# LVDS.net
KiCad netlist of a schematic drawn in Altium Designer
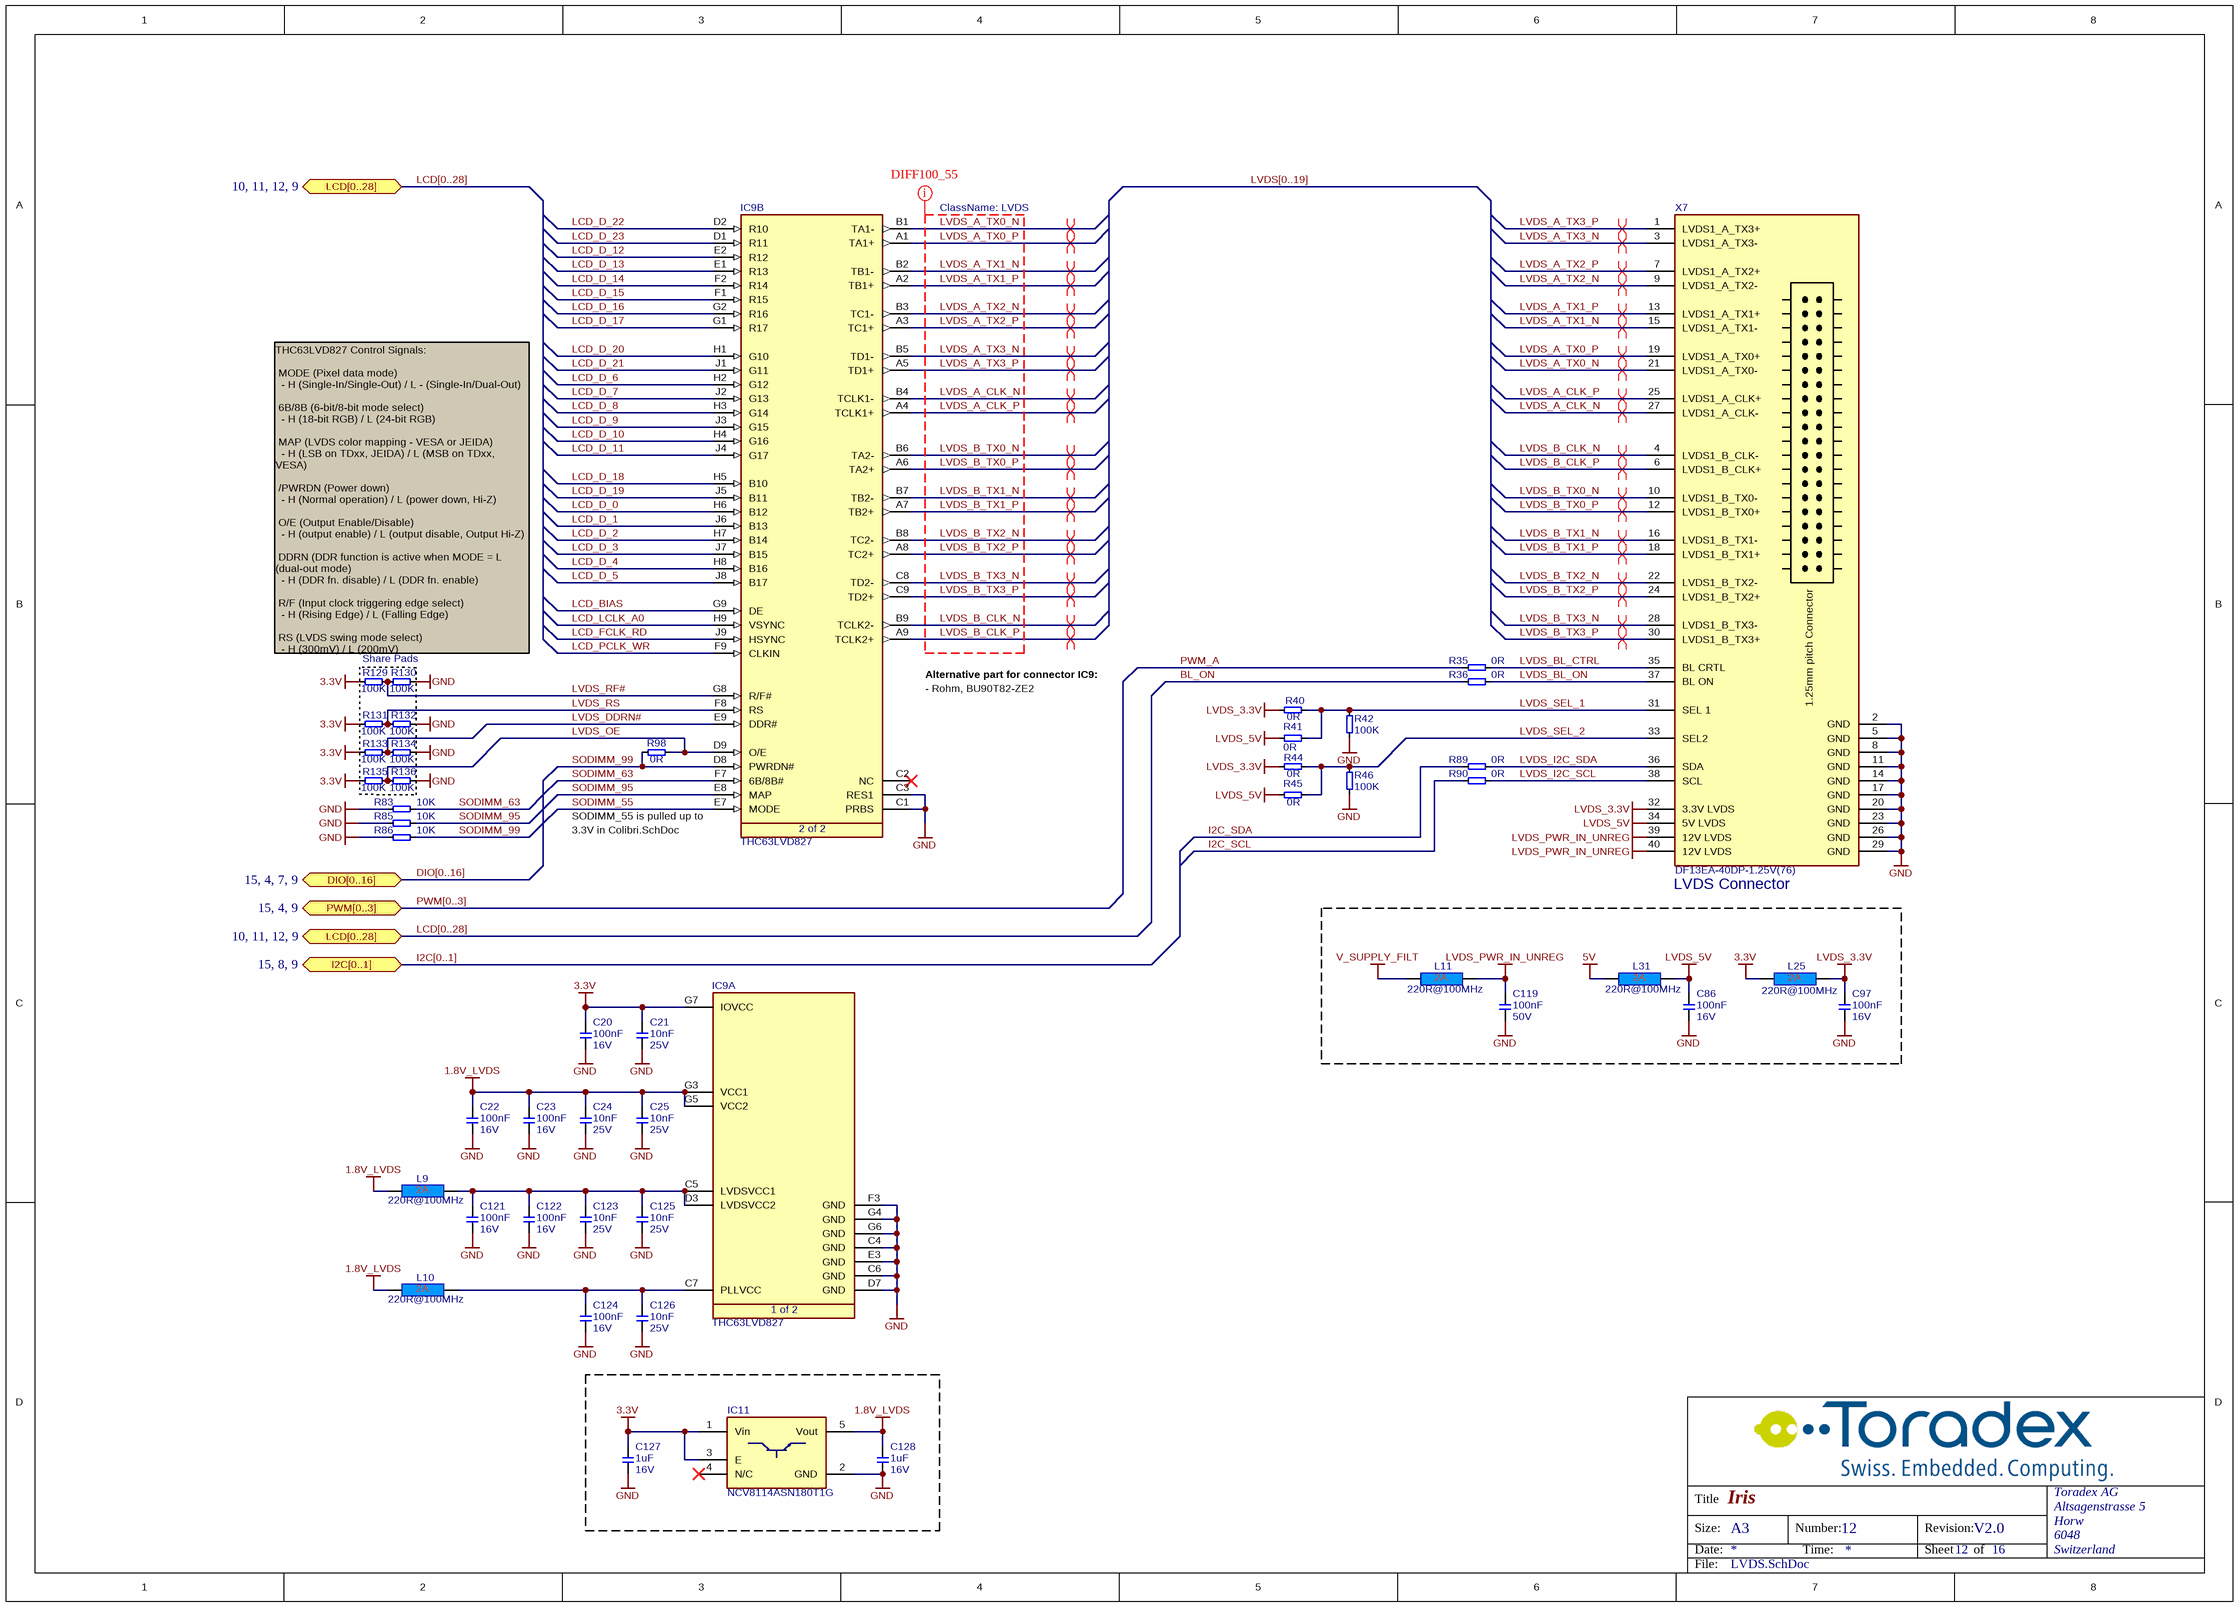
[diagram p0: LVDS.SchDoc]

(export (version "E")
  (design (tool "Eeschema 10.0.6"))
  (components
    (comp (ref "C20")
      (value "100nF")
      (footprint "CAPC1005X60N")
      (description "Capacitor Ceramic X7R 100nF 16V 10% 0402")
      (fields (field (name "TOLERANCE") "10%") (field (name "RATING") "16V"))
      (libsource (lib "Iris") (part "C-X7R-100nF-16V-10%-0402"))
    )
    (comp (ref "C21")
      (value "10nF")
      (footprint "CAPC1005X60N")
      (description "Capacitor Ceramic X7R 10nF 25V 10% 0402")
      (fields (field (name "TOLERANCE") "10%") (field (name "RATING") "25V"))
      (libsource (lib "Iris") (part "C-X7R-10nF-25V-10%-0402"))
    )
    (comp (ref "C22")
      (value "100nF")
      (footprint "CAPC1005X60N")
      (description "Capacitor Ceramic X7R 100nF 16V 10% 0402")
      (fields (field (name "TOLERANCE") "10%") (field (name "RATING") "16V"))
      (libsource (lib "Iris") (part "C-X7R-100nF-16V-10%-0402"))
    )
    (comp (ref "C23")
      (value "100nF")
      (footprint "CAPC1005X60N")
      (description "Capacitor Ceramic X7R 100nF 16V 10% 0402")
      (fields (field (name "TOLERANCE") "10%") (field (name "RATING") "16V"))
      (libsource (lib "Iris") (part "C-X7R-100nF-16V-10%-0402"))
    )
    (comp (ref "C24")
      (value "10nF")
      (footprint "CAPC1005X60N")
      (description "Capacitor Ceramic X7R 10nF 25V 10% 0402")
      (fields (field (name "TOLERANCE") "10%") (field (name "RATING") "25V"))
      (libsource (lib "Iris") (part "C-X7R-10nF-25V-10%-0402"))
    )
    (comp (ref "C25")
      (value "10nF")
      (footprint "CAPC1005X60N")
      (description "Capacitor Ceramic X7R 10nF 25V 10% 0402")
      (fields (field (name "TOLERANCE") "10%") (field (name "RATING") "25V"))
      (libsource (lib "Iris") (part "C-X7R-10nF-25V-10%-0402"))
    )
    (comp (ref "C86")
      (value "100nF")
      (footprint "CAPC1005X60N")
      (description "Capacitor Ceramic X7R 100nF 16V 10% 0402")
      (fields (field (name "TOLERANCE") "10%") (field (name "RATING") "16V"))
      (libsource (lib "Iris") (part "C-X7R-100nF-16V-10%-0402"))
    )
    (comp (ref "C97")
      (value "100nF")
      (footprint "CAPC1005X60N")
      (description "Capacitor Ceramic X7R 100nF 16V 10% 0402")
      (fields (field (name "TOLERANCE") "10%") (field (name "RATING") "16V"))
      (libsource (lib "Iris") (part "C-X7R-100nF-16V-10%-0402"))
    )
    (comp (ref "C119")
      (value "100nF")
      (footprint "T_CAPC0603X33N")
      (description "Capacitor Ceramic X7R 100nF 50V 10% 0603")
      (fields (field (name "TOLERANCE") "10%") (field (name "RATING") "50V"))
      (libsource (lib "Iris") (part "C-X7R-100nF-50V-10%-0603"))
    )
    (comp (ref "C121")
      (value "100nF")
      (footprint "CAPC1005X60N")
      (description "Capacitor Ceramic X7R 100nF 16V 10% 0402")
      (fields (field (name "TOLERANCE") "10%") (field (name "RATING") "16V"))
      (libsource (lib "Iris") (part "C-X7R-100nF-16V-10%-0402"))
    )
    (comp (ref "C122")
      (value "100nF")
      (footprint "CAPC1005X60N")
      (description "Capacitor Ceramic X7R 100nF 16V 10% 0402")
      (fields (field (name "TOLERANCE") "10%") (field (name "RATING") "16V"))
      (libsource (lib "Iris") (part "C-X7R-100nF-16V-10%-0402"))
    )
    (comp (ref "C123")
      (value "10nF")
      (footprint "CAPC1005X60N")
      (description "Capacitor Ceramic X7R 10nF 25V 10% 0402")
      (fields (field (name "TOLERANCE") "10%") (field (name "RATING") "25V"))
      (libsource (lib "Iris") (part "C-X7R-10nF-25V-10%-0402"))
    )
    (comp (ref "C124")
      (value "100nF")
      (footprint "CAPC1005X60N")
      (description "Capacitor Ceramic X7R 100nF 16V 10% 0402")
      (fields (field (name "TOLERANCE") "10%") (field (name "RATING") "16V"))
      (libsource (lib "Iris") (part "C-X7R-100nF-16V-10%-0402"))
    )
    (comp (ref "C125")
      (value "10nF")
      (footprint "CAPC1005X60N")
      (description "Capacitor Ceramic X7R 10nF 25V 10% 0402")
      (fields (field (name "TOLERANCE") "10%") (field (name "RATING") "25V"))
      (libsource (lib "Iris") (part "C-X7R-10nF-25V-10%-0402"))
    )
    (comp (ref "C126")
      (value "10nF")
      (footprint "CAPC1005X60N")
      (description "Capacitor Ceramic X7R 10nF 25V 10% 0402")
      (fields (field (name "TOLERANCE") "10%") (field (name "RATING") "25V"))
      (libsource (lib "Iris") (part "C-X7R-10nF-25V-10%-0402"))
    )
    (comp (ref "C127")
      (value "1uF")
      (footprint "T_CAPC0603X33N")
      (description "Capacitor Ceramic X5R 1uF 16V 10% 0603")
      (fields (field (name "TOLERANCE") "10%") (field (name "RATING") "16V"))
      (libsource (lib "Iris") (part "C-X5R-1uF-16V-10%-0603"))
    )
    (comp (ref "C128")
      (value "1uF")
      (footprint "T_CAPC0603X33N")
      (description "Capacitor Ceramic X5R 1uF 16V 10% 0603")
      (fields (field (name "TOLERANCE") "10%") (field (name "RATING") "16V"))
      (libsource (lib "Iris") (part "C-X5R-1uF-16V-10%-0603"))
    )
    (comp (ref "IC9")
      (value "THC63LVD827")
      (footprint "BGA72C65P9X9_700X700X120")
      (description "LVDS Transmitter")
      (fields (field (name "MANUFACTURER PART NO.") "THC63LVD827"))
      (libsource (lib "Iris") (part "IC-THine-THC63LVD827"))
    )
    (comp (ref "IC11")
      (value "NCV8114ASN180T1G")
      (footprint "SOT95P279X142-5N")
      (description "LDO regulator, Vout = 1.8V, Imax = 300mA")
      (fields (field (name "MANUFACTURER PART NO.") "NCV8114ASN180T1G"))
      (libsource (lib "Iris") (part "IC-OnSemi-NCV8114ASN180T1G"))
    )
    (comp (ref "L9")
      (value "220R@100MHz")
      (footprint "INDC1608X95N")
      (description "220R@100MHz 2A EMI FILTER")
      (fields (field (name "TOLERANCE") "25%"))
      (libsource (lib "Iris") (part "L-220R@100MHz-2A-25%-0603"))
    )
    (comp (ref "L10")
      (value "220R@100MHz")
      (footprint "INDC1608X95N")
      (description "220R@100MHz 2A EMI FILTER")
      (fields (field (name "TOLERANCE") "25%"))
      (libsource (lib "Iris") (part "L-220R@100MHz-2A-25%-0603"))
    )
    (comp (ref "L11")
      (value "220R@100MHz")
      (footprint "INDC1608X95N")
      (description "220R@100MHz 2A EMI FILTER")
      (fields (field (name "TOLERANCE") "25%"))
      (libsource (lib "Iris") (part "L-220R@100MHz-2A-25%-0603"))
    )
    (comp (ref "L25")
      (value "220R@100MHz")
      (footprint "INDC1608X95N")
      (description "220R@100MHz 2A EMI FILTER")
      (fields (field (name "TOLERANCE") "25%"))
      (libsource (lib "Iris") (part "L-220R@100MHz-2A-25%-0603"))
    )
    (comp (ref "L31")
      (value "220R@100MHz")
      (footprint "INDC1608X95N")
      (description "220R@100MHz 2A EMI FILTER")
      (fields (field (name "TOLERANCE") "25%"))
      (libsource (lib "Iris") (part "L-220R@100MHz-2A-25%-0603"))
    )
    (comp (ref "R35")
      (value "0R")
      (footprint "T_RESC0603X30N")
      (description "Resistor 0 ohm 63mW 5% 0603")
      (fields (field (name "TOLERANCE") "5%"))
      (libsource (lib "Iris") (part "R-0R-63mW-5%-0603"))
    )
    (comp (ref "R36")
      (value "0R")
      (footprint "T_RESC0603X30N")
      (description "Resistor 0 ohm 63mW 5% 0603")
      (fields (field (name "TOLERANCE") "5%"))
      (libsource (lib "Iris") (part "R-0R-63mW-5%-0603"))
    )
    (comp (ref "R40")
      (value "0R")
      (footprint "T_RESC0603X30N")
      (description "Resistor 0 ohm 63mW 5% 0603")
      (fields (field (name "TOLERANCE") "5%"))
      (libsource (lib "Iris") (part "R-0R-63mW-5%-0603"))
    )
    (comp (ref "R41")
      (value "0R")
      (footprint "T_RESC0603X30N")
      (description "Resistor 0 ohm 63mW 5% 0603")
      (fields (field (name "TOLERANCE") "5%"))
      (libsource (lib "Iris") (part "R-0R-63mW-5%-0603"))
    )
    (comp (ref "R42")
      (value "100K")
      (footprint "T_RESC0603X30N")
      (description "Resistor 100 Kohm 63mW 5% 0603")
      (fields (field (name "TOLERANCE") "5%"))
      (libsource (lib "Iris") (part "R-100KR-63mW-5%-0603"))
    )
    (comp (ref "R44")
      (value "0R")
      (footprint "T_RESC0603X30N")
      (description "Resistor 0 ohm 63mW 5% 0603")
      (fields (field (name "TOLERANCE") "5%"))
      (libsource (lib "Iris") (part "R-0R-63mW-5%-0603"))
    )
    (comp (ref "R45")
      (value "0R")
      (footprint "T_RESC0603X30N")
      (description "Resistor 0 ohm 63mW 5% 0603")
      (fields (field (name "TOLERANCE") "5%"))
      (libsource (lib "Iris") (part "R-0R-63mW-5%-0603"))
    )
    (comp (ref "R46")
      (value "100K")
      (footprint "T_RESC0603X30N")
      (description "Resistor 100 Kohm 63mW 5% 0603")
      (fields (field (name "TOLERANCE") "5%"))
      (libsource (lib "Iris") (part "R-100KR-63mW-5%-0603"))
    )
    (comp (ref "R83")
      (value "10K")
      (footprint "T_RESC0603X30N")
      (description "Resistor 10 Kohm 63mW 5% 0603")
      (fields (field (name "TOLERANCE") "5%"))
      (libsource (lib "Iris") (part "R-10KR-63mW-5%-0603"))
    )
    (comp (ref "R85")
      (value "10K")
      (footprint "T_RESC0603X30N")
      (description "Resistor 10 Kohm 63mW 5% 0603")
      (fields (field (name "TOLERANCE") "5%"))
      (libsource (lib "Iris") (part "R-10KR-63mW-5%-0603"))
    )
    (comp (ref "R86")
      (value "10K")
      (footprint "T_RESC0603X30N")
      (description "Resistor 10 Kohm 63mW 5% 0603")
      (fields (field (name "TOLERANCE") "5%"))
      (libsource (lib "Iris") (part "R-10KR-63mW-5%-0603"))
    )
    (comp (ref "R89")
      (value "0R")
      (footprint "T_RESC0603X30N")
      (description "Resistor 0 ohm 63mW 5% 0603")
      (fields (field (name "TOLERANCE") "5%"))
      (libsource (lib "Iris") (part "R-0R-63mW-5%-0603"))
    )
    (comp (ref "R90")
      (value "0R")
      (footprint "T_RESC0603X30N")
      (description "Resistor 0 ohm 63mW 5% 0603")
      (fields (field (name "TOLERANCE") "5%"))
      (libsource (lib "Iris") (part "R-0R-63mW-5%-0603"))
    )
    (comp (ref "R98")
      (value "0R")
      (footprint "T_RESC0603X30N")
      (description "Resistor 0 ohm 63mW 5% 0603")
      (fields (field (name "TOLERANCE") "5%"))
      (libsource (lib "Iris") (part "R-0R-63mW-5%-0603"))
    )
    (comp (ref "R129")
      (value "100K")
      (footprint "T_RESC0603X30N")
      (description "Resistor 100 Kohm 63mW 5% 0603")
      (fields (field (name "TOLERANCE") "5%"))
      (libsource (lib "Iris") (part "R-100KR-63mW-5%-0603"))
    )
    (comp (ref "R130")
      (value "100K")
      (footprint "T_RESC0603X30N")
      (description "Resistor 100 Kohm 63mW 5% 0603")
      (fields (field (name "TOLERANCE") "5%"))
      (libsource (lib "Iris") (part "R-100KR-63mW-5%-0603"))
    )
    (comp (ref "R131")
      (value "100K")
      (footprint "T_RESC0603X30N")
      (description "Resistor 100 Kohm 63mW 5% 0603")
      (fields (field (name "TOLERANCE") "5%"))
      (libsource (lib "Iris") (part "R-100KR-63mW-5%-0603"))
    )
    (comp (ref "R132")
      (value "100K")
      (footprint "T_RESC0603X30N")
      (description "Resistor 100 Kohm 63mW 5% 0603")
      (fields (field (name "TOLERANCE") "5%"))
      (libsource (lib "Iris") (part "R-100KR-63mW-5%-0603"))
    )
    (comp (ref "R133")
      (value "100K")
      (footprint "T_RESC0603X30N")
      (description "Resistor 100 Kohm 63mW 5% 0603")
      (fields (field (name "TOLERANCE") "5%"))
      (libsource (lib "Iris") (part "R-100KR-63mW-5%-0603"))
    )
    (comp (ref "R134")
      (value "100K")
      (footprint "T_RESC0603X30N")
      (description "Resistor 100 Kohm 63mW 5% 0603")
      (fields (field (name "TOLERANCE") "5%"))
      (libsource (lib "Iris") (part "R-100KR-63mW-5%-0603"))
    )
    (comp (ref "R135")
      (value "100K")
      (footprint "T_RESC0603X30N")
      (description "Resistor 100 Kohm 63mW 5% 0603")
      (fields (field (name "TOLERANCE") "5%"))
      (libsource (lib "Iris") (part "R-100KR-63mW-5%-0603"))
    )
    (comp (ref "R136")
      (value "100K")
      (footprint "T_RESC0603X30N")
      (description "Resistor 100 Kohm 63mW 5% 0603")
      (fields (field (name "TOLERANCE") "5%"))
      (libsource (lib "Iris") (part "R-100KR-63mW-5%-0603"))
    )
    (comp (ref "X7")
      (value "DF13EA-40DP-1.25V(76)")
      (footprint "T_HIROSE_DF13A-40DP-1.25V(55)")
      (description "LVDS Connector, 2x20 pin, 1.25mm pitch, SMD")
      (fields (field (name "MANUFACTURER PART NO.") "DF13EA-40DP-1.25V(76)"))
      (libsource (lib "Iris") (part "CON-Hirose-DF13EA-40DP-1.25V(76)"))
    )
  )
  (nets
    (net (code "73") (name "/BL_ON") (class "Default")
      (node (ref "R36") (pin "2") (pinfunction "2_2") (pintype "passive"))
    )
    (net (code "76") (name "/I2C_SCL") (class "Default")
      (node (ref "R90") (pin "1") (pinfunction "1_1") (pintype "passive"))
    )
    (net (code "77") (name "/I2C_SDA") (class "Default")
      (node (ref "R89") (pin "1") (pinfunction "1_1") (pintype "passive"))
    )
    (net (code "79") (name "/LCD_BIAS") (class "Default")
      (node (ref "IC9") (pin "G9") (pinfunction "DE_G9") (pintype "input"))
    )
    (net (code "80") (name "/LCD_D_0") (class "Default")
      (node (ref "IC9") (pin "H6") (pinfunction "B12_H6") (pintype "input"))
    )
    (net (code "81") (name "/LCD_D_1") (class "Default")
      (node (ref "IC9") (pin "J6") (pinfunction "B13_J6") (pintype "input"))
    )
    (net (code "82") (name "/LCD_D_2") (class "Default")
      (node (ref "IC9") (pin "H7") (pinfunction "B14_H7") (pintype "input"))
    )
    (net (code "83") (name "/LCD_D_3") (class "Default")
      (node (ref "IC9") (pin "J7") (pinfunction "B15_J7") (pintype "input"))
    )
    (net (code "84") (name "/LCD_D_4") (class "Default")
      (node (ref "IC9") (pin "H8") (pinfunction "B16_H8") (pintype "input"))
    )
    (net (code "85") (name "/LCD_D_5") (class "Default")
      (node (ref "IC9") (pin "J8") (pinfunction "B17_J8") (pintype "input"))
    )
    (net (code "86") (name "/LCD_D_6") (class "Default")
      (node (ref "IC9") (pin "H2") (pinfunction "G12_H2") (pintype "input"))
    )
    (net (code "87") (name "/LCD_D_7") (class "Default")
      (node (ref "IC9") (pin "J2") (pinfunction "G13_J2") (pintype "input"))
    )
    (net (code "88") (name "/LCD_D_8") (class "Default")
      (node (ref "IC9") (pin "H3") (pinfunction "G14_H3") (pintype "input"))
    )
    (net (code "89") (name "/LCD_D_9") (class "Default")
      (node (ref "IC9") (pin "J3") (pinfunction "G15_J3") (pintype "input"))
    )
    (net (code "90") (name "/LCD_D_10") (class "Default")
      (node (ref "IC9") (pin "H4") (pinfunction "G16_H4") (pintype "input"))
    )
    (net (code "91") (name "/LCD_D_11") (class "Default")
      (node (ref "IC9") (pin "J4") (pinfunction "G17_J4") (pintype "input"))
    )
    (net (code "92") (name "/LCD_D_12") (class "Default")
      (node (ref "IC9") (pin "E2") (pinfunction "R12_E2") (pintype "input"))
    )
    (net (code "93") (name "/LCD_D_13") (class "Default")
      (node (ref "IC9") (pin "E1") (pinfunction "R13_E1") (pintype "input"))
    )
    (net (code "94") (name "/LCD_D_14") (class "Default")
      (node (ref "IC9") (pin "F2") (pinfunction "R14_F2") (pintype "input"))
    )
    (net (code "95") (name "/LCD_D_15") (class "Default")
      (node (ref "IC9") (pin "F1") (pinfunction "R15_F1") (pintype "input"))
    )
    (net (code "96") (name "/LCD_D_16") (class "Default")
      (node (ref "IC9") (pin "G2") (pinfunction "R16_G2") (pintype "input"))
    )
    (net (code "97") (name "/LCD_D_17") (class "Default")
      (node (ref "IC9") (pin "G1") (pinfunction "R17_G1") (pintype "input"))
    )
    (net (code "98") (name "/LCD_D_18") (class "Default")
      (node (ref "IC9") (pin "H5") (pinfunction "B10_H5") (pintype "input"))
    )
    (net (code "99") (name "/LCD_D_19") (class "Default")
      (node (ref "IC9") (pin "J5") (pinfunction "B11_J5") (pintype "input"))
    )
    (net (code "100") (name "/LCD_D_20") (class "Default")
      (node (ref "IC9") (pin "H1") (pinfunction "G10_H1") (pintype "input"))
    )
    (net (code "101") (name "/LCD_D_21") (class "Default")
      (node (ref "IC9") (pin "J1") (pinfunction "G11_J1") (pintype "input"))
    )
    (net (code "102") (name "/LCD_D_22") (class "Default")
      (node (ref "IC9") (pin "D2") (pinfunction "R10_D2") (pintype "input"))
    )
    (net (code "103") (name "/LCD_D_23") (class "Default")
      (node (ref "IC9") (pin "D1") (pinfunction "R11_D1") (pintype "input"))
    )
    (net (code "104") (name "/LCD_FCLK_RD") (class "Default")
      (node (ref "IC9") (pin "J9") (pinfunction "HSYNC_J9") (pintype "input"))
    )
    (net (code "105") (name "/LCD_LCLK_A0") (class "Default")
      (node (ref "IC9") (pin "H9") (pinfunction "VSYNC_H9") (pintype "input"))
    )
    (net (code "106") (name "/LCD_PCLK_WR") (class "Default")
      (node (ref "IC9") (pin "F9") (pinfunction "CLKIN_F9") (pintype "input"))
    )
    (net (code "108") (name "/LVDS_A_CLK_N") (class "Default")
      (node (ref "IC9") (pin "B4") (pinfunction "TCLK1-_B4") (pintype "output"))
      (node (ref "X7") (pin "27") (pinfunction "LVDS1_A_CLK-_27") (pintype "passive"))
    )
    (net (code "109") (name "/LVDS_A_CLK_P") (class "Default")
      (node (ref "IC9") (pin "A4") (pinfunction "TCLK1+_A4") (pintype "output"))
      (node (ref "X7") (pin "25") (pinfunction "LVDS1_A_CLK+_25") (pintype "passive"))
    )
    (net (code "110") (name "/LVDS_A_TX0_N") (class "Default")
      (node (ref "IC9") (pin "B1") (pinfunction "TA1-_B1") (pintype "output"))
      (node (ref "X7") (pin "21") (pinfunction "LVDS1_A_TX0-_21") (pintype "passive"))
    )
    (net (code "111") (name "/LVDS_A_TX0_P") (class "Default")
      (node (ref "IC9") (pin "A1") (pinfunction "TA1+_A1") (pintype "output"))
      (node (ref "X7") (pin "19") (pinfunction "LVDS1_A_TX0+_19") (pintype "passive"))
    )
    (net (code "112") (name "/LVDS_A_TX1_N") (class "Default")
      (node (ref "IC9") (pin "B2") (pinfunction "TB1-_B2") (pintype "output"))
      (node (ref "X7") (pin "15") (pinfunction "LVDS1_A_TX1-_15") (pintype "passive"))
    )
    (net (code "113") (name "/LVDS_A_TX1_P") (class "Default")
      (node (ref "IC9") (pin "A2") (pinfunction "TB1+_A2") (pintype "output"))
      (node (ref "X7") (pin "13") (pinfunction "LVDS1_A_TX1+_13") (pintype "passive"))
    )
    (net (code "114") (name "/LVDS_A_TX2_N") (class "Default")
      (node (ref "IC9") (pin "B3") (pinfunction "TC1-_B3") (pintype "output"))
      (node (ref "X7") (pin "9") (pinfunction "LVDS1_A_TX2-_9") (pintype "passive"))
    )
    (net (code "115") (name "/LVDS_A_TX2_P") (class "Default")
      (node (ref "IC9") (pin "A3") (pinfunction "TC1+_A3") (pintype "output"))
      (node (ref "X7") (pin "7") (pinfunction "LVDS1_A_TX2+_7") (pintype "passive"))
    )
    (net (code "116") (name "/LVDS_A_TX3_N") (class "Default")
      (node (ref "IC9") (pin "B5") (pinfunction "TD1-_B5") (pintype "output"))
      (node (ref "X7") (pin "3") (pinfunction "LVDS1_A_TX3-_3") (pintype "passive"))
    )
    (net (code "117") (name "/LVDS_A_TX3_P") (class "Default")
      (node (ref "IC9") (pin "A5") (pinfunction "TD1+_A5") (pintype "output"))
      (node (ref "X7") (pin "1") (pinfunction "LVDS1_A_TX3+_1") (pintype "passive"))
    )
    (net (code "118") (name "/LVDS_BL_CTRL") (class "Default")
      (node (ref "R35") (pin "1") (pinfunction "1_1") (pintype "passive"))
      (node (ref "X7") (pin "35") (pinfunction "BL_CRTL_35") (pintype "passive"))
    )
    (net (code "119") (name "/LVDS_BL_ON") (class "Default")
      (node (ref "R36") (pin "1") (pinfunction "1_1") (pintype "passive"))
      (node (ref "X7") (pin "37") (pinfunction "BL_ON_37") (pintype "passive"))
    )
    (net (code "120") (name "/LVDS_B_CLK_N") (class "Default")
      (node (ref "IC9") (pin "B9") (pinfunction "TCLK2-_B9") (pintype "output"))
      (node (ref "X7") (pin "4") (pinfunction "LVDS1_B_CLK-_4") (pintype "passive"))
    )
    (net (code "121") (name "/LVDS_B_CLK_P") (class "Default")
      (node (ref "IC9") (pin "A9") (pinfunction "TCLK2+_A9") (pintype "output"))
      (node (ref "X7") (pin "6") (pinfunction "LVDS1_B_CLK+_6") (pintype "passive"))
    )
    (net (code "122") (name "/LVDS_B_TX0_N") (class "Default")
      (node (ref "IC9") (pin "B6") (pinfunction "TA2-_B6") (pintype "output"))
      (node (ref "X7") (pin "10") (pinfunction "LVDS1_B_TX0-_10") (pintype "passive"))
    )
    (net (code "123") (name "/LVDS_B_TX0_P") (class "Default")
      (node (ref "IC9") (pin "A6") (pinfunction "TA2+_A6") (pintype "output"))
      (node (ref "X7") (pin "12") (pinfunction "LVDS1_B_TX0+_12") (pintype "passive"))
    )
    (net (code "124") (name "/LVDS_B_TX1_N") (class "Default")
      (node (ref "IC9") (pin "B7") (pinfunction "TB2-_B7") (pintype "output"))
      (node (ref "X7") (pin "16") (pinfunction "LVDS1_B_TX1-_16") (pintype "passive"))
    )
    (net (code "125") (name "/LVDS_B_TX1_P") (class "Default")
      (node (ref "IC9") (pin "A7") (pinfunction "TB2+_A7") (pintype "output"))
      (node (ref "X7") (pin "18") (pinfunction "LVDS1_B_TX1+_18") (pintype "passive"))
    )
    (net (code "126") (name "/LVDS_B_TX2_N") (class "Default")
      (node (ref "IC9") (pin "B8") (pinfunction "TC2-_B8") (pintype "output"))
      (node (ref "X7") (pin "22") (pinfunction "LVDS1_B_TX2-_22") (pintype "passive"))
    )
    (net (code "127") (name "/LVDS_B_TX2_P") (class "Default")
      (node (ref "IC9") (pin "A8") (pinfunction "TC2+_A8") (pintype "output"))
      (node (ref "X7") (pin "24") (pinfunction "LVDS1_B_TX2+_24") (pintype "passive"))
    )
    (net (code "128") (name "/LVDS_B_TX3_N") (class "Default")
      (node (ref "IC9") (pin "C8") (pinfunction "TD2-_C8") (pintype "output"))
      (node (ref "X7") (pin "28") (pinfunction "LVDS1_B_TX3-_28") (pintype "passive"))
    )
    (net (code "129") (name "/LVDS_B_TX3_P") (class "Default")
      (node (ref "IC9") (pin "C9") (pinfunction "TD2+_C9") (pintype "output"))
      (node (ref "X7") (pin "30") (pinfunction "LVDS1_B_TX3+_30") (pintype "passive"))
    )
    (net (code "130") (name "/LVDS_DDRN#") (class "Default")
      (node (ref "IC9") (pin "E9") (pinfunction "DDR#_E9") (pintype "input"))
      (node (ref "R133") (pin "2") (pinfunction "2_2") (pintype "passive"))
      (node (ref "R134") (pin "1") (pinfunction "1_1") (pintype "passive"))
    )
    (net (code "131") (name "/LVDS_I2C_SCL") (class "Default")
      (node (ref "R90") (pin "2") (pinfunction "2_2") (pintype "passive"))
      (node (ref "X7") (pin "38") (pinfunction "SCL_38") (pintype "passive"))
    )
    (net (code "132") (name "/LVDS_I2C_SDA") (class "Default")
      (node (ref "R89") (pin "2") (pinfunction "2_2") (pintype "passive"))
      (node (ref "X7") (pin "36") (pinfunction "SDA_36") (pintype "passive"))
    )
    (net (code "133") (name "/LVDS_OE") (class "Default")
      (node (ref "IC9") (pin "D9") (pinfunction "O/E_D9") (pintype "input"))
      (node (ref "R135") (pin "2") (pinfunction "2_2") (pintype "passive"))
      (node (ref "R136") (pin "1") (pinfunction "1_1") (pintype "passive"))
      (node (ref "R98") (pin "2") (pinfunction "2_2") (pintype "passive"))
    )
    (net (code "134") (name "/LVDS_RF#") (class "Default")
      (node (ref "IC9") (pin "G8") (pinfunction "R/F#_G8") (pintype "input"))
      (node (ref "R129") (pin "2") (pinfunction "2_2") (pintype "passive"))
      (node (ref "R130") (pin "1") (pinfunction "1_1") (pintype "passive"))
    )
    (net (code "135") (name "/LVDS_RS") (class "Default")
      (node (ref "IC9") (pin "F8") (pinfunction "RS_F8") (pintype "input"))
      (node (ref "R131") (pin "2") (pinfunction "2_2") (pintype "passive"))
      (node (ref "R132") (pin "1") (pinfunction "1_1") (pintype "passive"))
    )
    (net (code "136") (name "/LVDS_SEL_1") (class "Default")
      (node (ref "R40") (pin "1") (pinfunction "1_1") (pintype "passive"))
      (node (ref "R41") (pin "2") (pinfunction "2_2") (pintype "passive"))
      (node (ref "R42") (pin "1") (pinfunction "1_1") (pintype "passive"))
      (node (ref "X7") (pin "31") (pinfunction "SEL_1_31") (pintype "passive"))
    )
    (net (code "137") (name "/LVDS_SEL_2") (class "Default")
      (node (ref "R44") (pin "2") (pinfunction "2_2") (pintype "passive"))
      (node (ref "R45") (pin "1") (pinfunction "1_1") (pintype "passive"))
      (node (ref "R46") (pin "1") (pinfunction "1_1") (pintype "passive"))
      (node (ref "X7") (pin "33") (pinfunction "SEL2_33") (pintype "passive"))
    )
    (net (code "139") (name "/PWM_A") (class "Default")
      (node (ref "R35") (pin "2") (pinfunction "2_2") (pintype "passive"))
    )
    (net (code "140") (name "/SODIMM_55") (class "Default")
      (node (ref "IC9") (pin "E7") (pinfunction "MODE_E7") (pintype "input"))
    )
    (net (code "141") (name "/SODIMM_63") (class "Default")
      (node (ref "IC9") (pin "F7") (pinfunction "6B/8B#_F7") (pintype "input"))
      (node (ref "R83") (pin "1") (pinfunction "1_1") (pintype "passive"))
    )
    (net (code "142") (name "/SODIMM_95") (class "Default")
      (node (ref "IC9") (pin "E8") (pinfunction "MAP_E8") (pintype "input"))
      (node (ref "R85") (pin "1") (pinfunction "1_1") (pintype "passive"))
    )
    (net (code "143") (name "/SODIMM_99") (class "Default")
      (node (ref "IC9") (pin "D8") (pinfunction "PWRDN#_D8") (pintype "input"))
      (node (ref "R86") (pin "1") (pinfunction "1_1") (pintype "passive"))
      (node (ref "R98") (pin "1") (pinfunction "1_1") (pintype "passive"))
    )
    (net (code "144") (name "1.8V_LVDS") (class "Default")
      (node (ref "C128") (pin "2") (pinfunction "2_2") (pintype "passive"))
      (node (ref "C22") (pin "2") (pinfunction "2_2") (pintype "passive"))
      (node (ref "C23") (pin "2") (pinfunction "2_2") (pintype "passive"))
      (node (ref "C24") (pin "2") (pinfunction "2_2") (pintype "passive"))
      (node (ref "C25") (pin "2") (pinfunction "2_2") (pintype "passive"))
      (node (ref "IC11") (pin "5") (pinfunction "Vout_5") (pintype "passive"))
      (node (ref "IC9") (pin "G3") (pinfunction "VCC1_G3") (pintype "power_in"))
      (node (ref "IC9") (pin "G5") (pinfunction "VCC2_G5") (pintype "power_in"))
      (node (ref "L10") (pin "1") (pinfunction "1_1") (pintype "passive"))
      (node (ref "L9") (pin "1") (pinfunction "1_1") (pintype "passive"))
    )
    (net (code "145") (name "3.3V") (class "Default")
      (node (ref "C127") (pin "2") (pinfunction "2_2") (pintype "passive"))
      (node (ref "C20") (pin "2") (pinfunction "2_2") (pintype "passive"))
      (node (ref "C21") (pin "2") (pinfunction "2_2") (pintype "passive"))
      (node (ref "IC11") (pin "1") (pinfunction "Vin_1") (pintype "passive"))
      (node (ref "IC11") (pin "3") (pinfunction "E_3") (pintype "passive"))
      (node (ref "IC9") (pin "G7") (pinfunction "IOVCC_G7") (pintype "power_in"))
      (node (ref "L25") (pin "1") (pinfunction "1_1") (pintype "passive"))
      (node (ref "R129") (pin "1") (pinfunction "1_1") (pintype "passive"))
      (node (ref "R131") (pin "1") (pinfunction "1_1") (pintype "passive"))
      (node (ref "R133") (pin "1") (pinfunction "1_1") (pintype "passive"))
      (node (ref "R135") (pin "1") (pinfunction "1_1") (pintype "passive"))
    )
    (net (code "146") (name "5V") (class "Default")
      (node (ref "L31") (pin "1") (pinfunction "1_1") (pintype "passive"))
    )
    (net (code "147") (name "GND") (class "Default")
      (node (ref "C119") (pin "1") (pinfunction "1_1") (pintype "passive"))
      (node (ref "C121") (pin "1") (pinfunction "1_1") (pintype "passive"))
      (node (ref "C122") (pin "1") (pinfunction "1_1") (pintype "passive"))
      (node (ref "C123") (pin "1") (pinfunction "1_1") (pintype "passive"))
      (node (ref "C124") (pin "1") (pinfunction "1_1") (pintype "passive"))
      (node (ref "C125") (pin "1") (pinfunction "1_1") (pintype "passive"))
      (node (ref "C126") (pin "1") (pinfunction "1_1") (pintype "passive"))
      (node (ref "C127") (pin "1") (pinfunction "1_1") (pintype "passive"))
      (node (ref "C128") (pin "1") (pinfunction "1_1") (pintype "passive"))
      (node (ref "C20") (pin "1") (pinfunction "1_1") (pintype "passive"))
      (node (ref "C21") (pin "1") (pinfunction "1_1") (pintype "passive"))
      (node (ref "C22") (pin "1") (pinfunction "1_1") (pintype "passive"))
      (node (ref "C23") (pin "1") (pinfunction "1_1") (pintype "passive"))
      (node (ref "C24") (pin "1") (pinfunction "1_1") (pintype "passive"))
      (node (ref "C25") (pin "1") (pinfunction "1_1") (pintype "passive"))
      (node (ref "C86") (pin "1") (pinfunction "1_1") (pintype "passive"))
      (node (ref "C97") (pin "1") (pinfunction "1_1") (pintype "passive"))
      (node (ref "IC11") (pin "2") (pinfunction "GND_2") (pintype "passive"))
      (node (ref "IC9") (pin "C1") (pinfunction "PRBS_C1") (pintype "power_in"))
      (node (ref "IC9") (pin "C3") (pinfunction "RES1_C3") (pintype "power_in"))
      (node (ref "IC9") (pin "C4") (pinfunction "GND_C4") (pintype "power_in"))
      (node (ref "IC9") (pin "C6") (pinfunction "GND_C6") (pintype "power_in"))
      (node (ref "IC9") (pin "D7") (pinfunction "GND_D7") (pintype "power_in"))
      (node (ref "IC9") (pin "E3") (pinfunction "GND_E3") (pintype "power_in"))
      (node (ref "IC9") (pin "F3") (pinfunction "GND_F3") (pintype "power_in"))
      (node (ref "IC9") (pin "G4") (pinfunction "GND_G4") (pintype "power_in"))
      (node (ref "IC9") (pin "G6") (pinfunction "GND_G6") (pintype "power_in"))
      (node (ref "R130") (pin "2") (pinfunction "2_2") (pintype "passive"))
      (node (ref "R132") (pin "2") (pinfunction "2_2") (pintype "passive"))
      (node (ref "R134") (pin "2") (pinfunction "2_2") (pintype "passive"))
      (node (ref "R136") (pin "2") (pinfunction "2_2") (pintype "passive"))
      (node (ref "R42") (pin "2") (pinfunction "2_2") (pintype "passive"))
      (node (ref "R46") (pin "2") (pinfunction "2_2") (pintype "passive"))
      (node (ref "R83") (pin "2") (pinfunction "2_2") (pintype "passive"))
      (node (ref "R85") (pin "2") (pinfunction "2_2") (pintype "passive"))
      (node (ref "R86") (pin "2") (pinfunction "2_2") (pintype "passive"))
      (node (ref "X7") (pin "11") (pinfunction "GND_11") (pintype "passive"))
      (node (ref "X7") (pin "14") (pinfunction "GND_14") (pintype "passive"))
      (node (ref "X7") (pin "17") (pinfunction "GND_17") (pintype "passive"))
      (node (ref "X7") (pin "2") (pinfunction "GND_2") (pintype "passive"))
      (node (ref "X7") (pin "20") (pinfunction "GND_20") (pintype "passive"))
      (node (ref "X7") (pin "23") (pinfunction "GND_23") (pintype "passive"))
      (node (ref "X7") (pin "26") (pinfunction "GND_26") (pintype "passive"))
      (node (ref "X7") (pin "29") (pinfunction "GND_29") (pintype "passive"))
      (node (ref "X7") (pin "5") (pinfunction "GND_5") (pintype "passive"))
      (node (ref "X7") (pin "8") (pinfunction "GND_8") (pintype "passive"))
    )
    (net (code "148") (name "LVDS_3.3V") (class "Default")
      (node (ref "C97") (pin "2") (pinfunction "2_2") (pintype "passive"))
      (node (ref "L25") (pin "2") (pinfunction "2_2") (pintype "passive"))
      (node (ref "R40") (pin "2") (pinfunction "2_2") (pintype "passive"))
      (node (ref "R44") (pin "1") (pinfunction "1_1") (pintype "passive"))
      (node (ref "X7") (pin "32") (pinfunction "3.3V_LVDS_32") (pintype "passive"))
    )
    (net (code "149") (name "LVDS_5V") (class "Default")
      (node (ref "C86") (pin "2") (pinfunction "2_2") (pintype "passive"))
      (node (ref "L31") (pin "2") (pinfunction "2_2") (pintype "passive"))
      (node (ref "R41") (pin "1") (pinfunction "1_1") (pintype "passive"))
      (node (ref "R45") (pin "2") (pinfunction "2_2") (pintype "passive"))
      (node (ref "X7") (pin "34") (pinfunction "5V_LVDS_34") (pintype "passive"))
    )
    (net (code "150") (name "LVDS_PWR_IN_UNREG") (class "Default")
      (node (ref "C119") (pin "2") (pinfunction "2_2") (pintype "passive"))
      (node (ref "L11") (pin "2") (pinfunction "2_2") (pintype "passive"))
      (node (ref "X7") (pin "39") (pinfunction "12V_LVDS_39") (pintype "passive"))
      (node (ref "X7") (pin "40") (pinfunction "12V_LVDS_40") (pintype "passive"))
    )
    (net (code "151") (name "Net-(IC9A-LVDSVCC1)") (class "Default")
      (node (ref "C121") (pin "2") (pinfunction "2_2") (pintype "passive"))
      (node (ref "C122") (pin "2") (pinfunction "2_2") (pintype "passive"))
      (node (ref "C123") (pin "2") (pinfunction "2_2") (pintype "passive"))
      (node (ref "C125") (pin "2") (pinfunction "2_2") (pintype "passive"))
      (node (ref "IC9") (pin "C5") (pinfunction "LVDSVCC1_C5") (pintype "power_in"))
      (node (ref "IC9") (pin "D3") (pinfunction "LVDSVCC2_D3") (pintype "power_in"))
      (node (ref "L9") (pin "2") (pinfunction "2_2") (pintype "passive"))
    )
    (net (code "152") (name "Net-(IC9A-PLLVCC)") (class "Default")
      (node (ref "C124") (pin "2") (pinfunction "2_2") (pintype "passive"))
      (node (ref "C126") (pin "2") (pinfunction "2_2") (pintype "passive"))
      (node (ref "IC9") (pin "C7") (pinfunction "PLLVCC_C7") (pintype "power_in"))
      (node (ref "L10") (pin "2") (pinfunction "2_2") (pintype "passive"))
    )
    (net (code "153") (name "V_SUPPLY_FILT") (class "Default")
      (node (ref "L11") (pin "1") (pinfunction "1_1") (pintype "passive"))
    )
    (net (code "154") (name "unconnected-(IC9B-NC-PadC2)") (class "Default")
      (node (ref "IC9") (pin "C2") (pinfunction "NC_C2") (pintype "power_in+no_connect"))
    )
    (net (code "155") (name "unconnected-(IC11-N{slash}C-Pad4)") (class "Default")
      (node (ref "IC11") (pin "4") (pinfunction "N/C_4") (pintype "passive+no_connect"))
    )
  )
)
